# ESenseFE-Power.net
KiCad netlist of a schematic drawn in Altium Designer
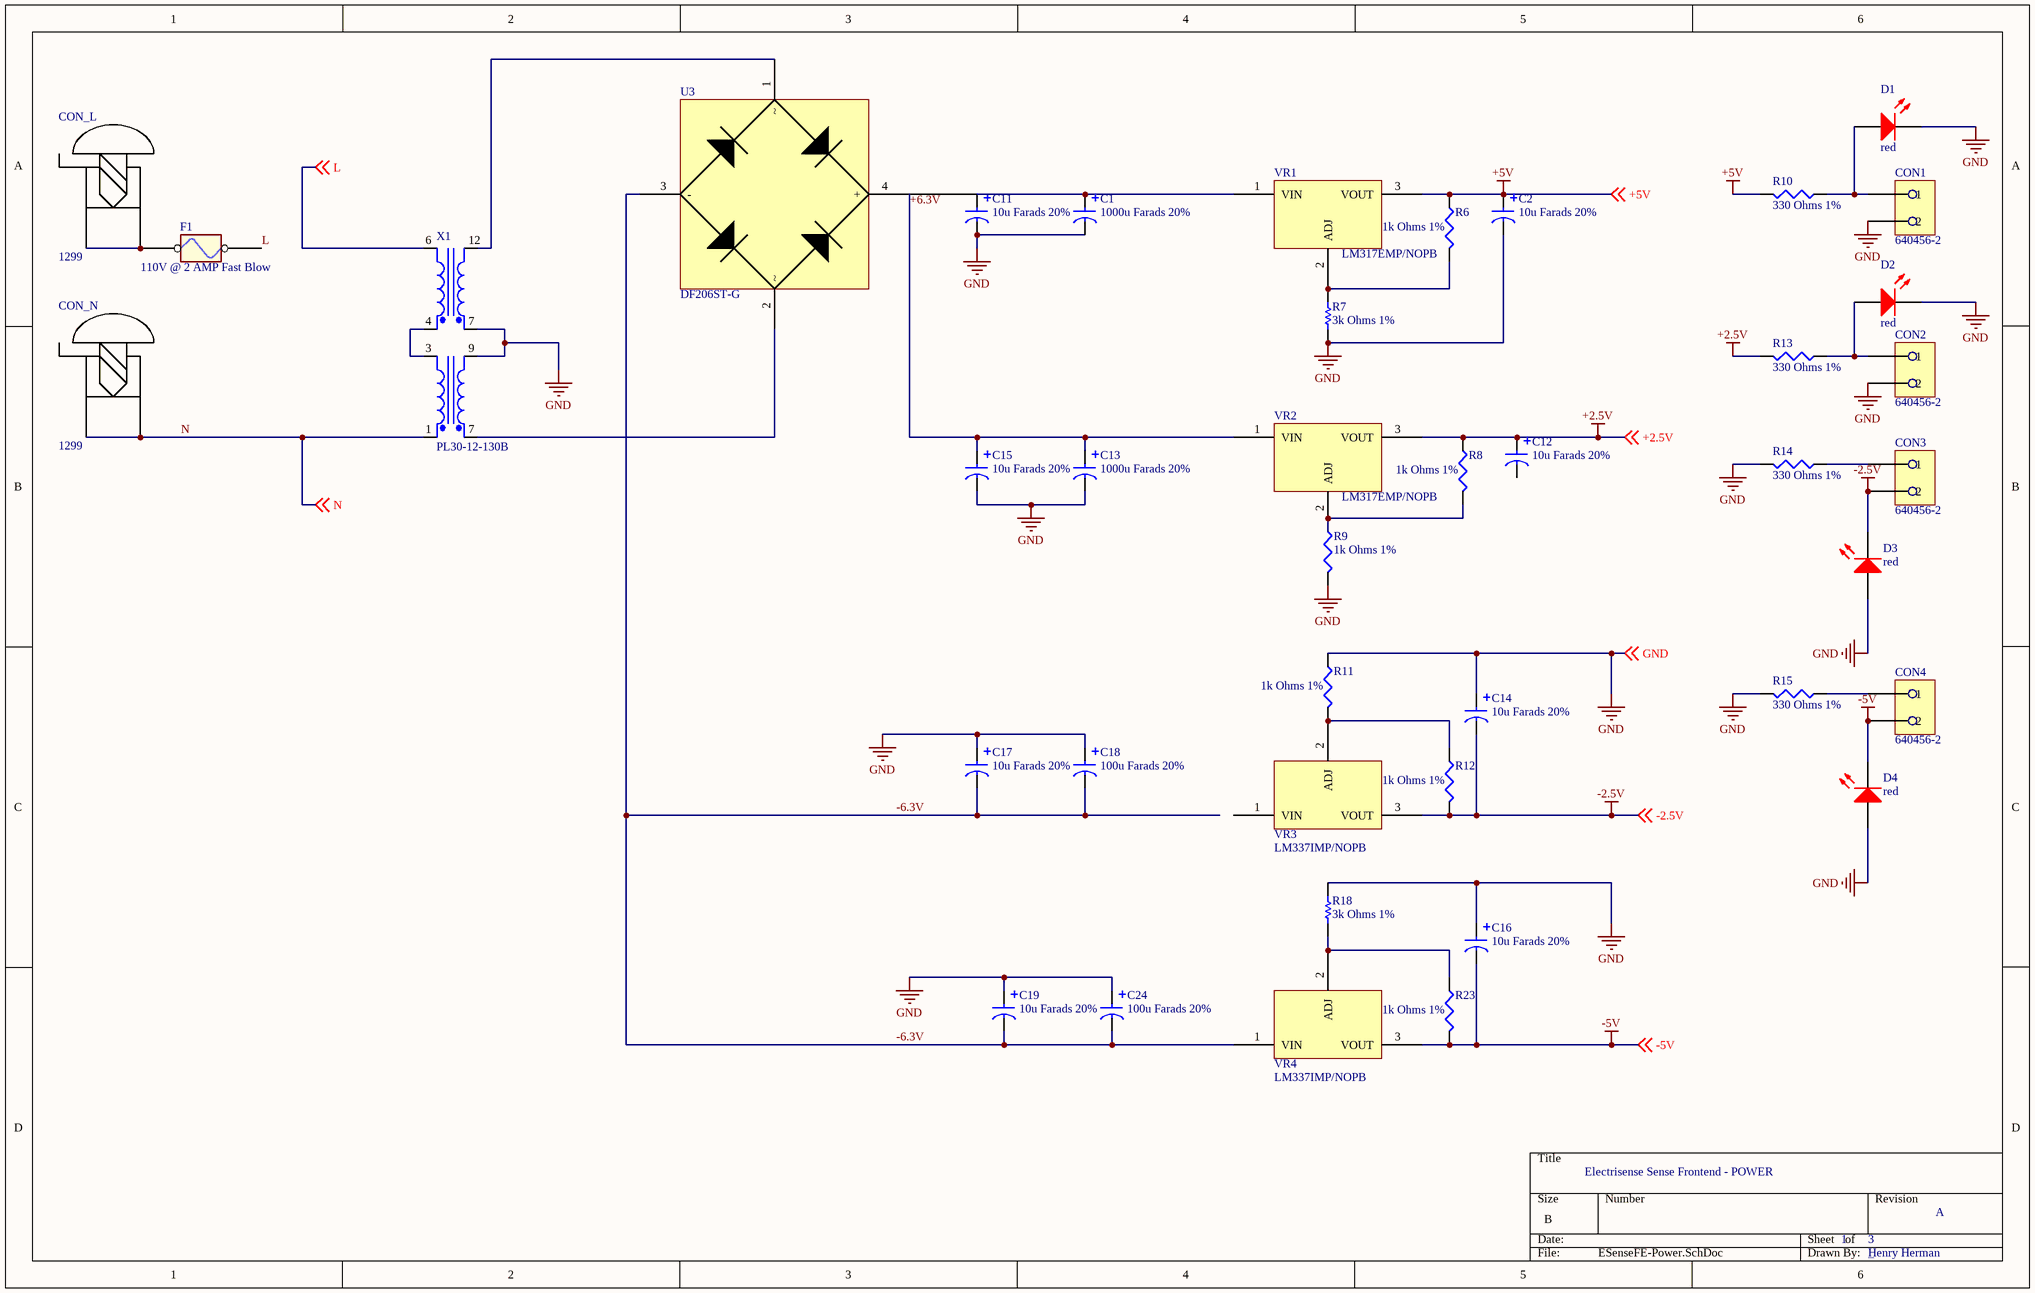
[diagram p0: ESenseFE-Power.SchDoc]

(export (version "E")
  (design (tool "Eeschema 10.0.6"))
  (components
    (comp (ref "C1")
      (value "1000u Farads 20%")
      (footprint "CAP-CAN-SMD-POL-12.5mmDia")
      (description "cap aluminum 1000uf 25vdc 20% 12.5 x 13.5mm smd 1100ma 5000")
      (fields (field (name "MFRPARTNUM") "EEV-FK1E102Q"))
      (libsource (lib "FriedParts") (part "CAP_POL"))
    )
    (comp (ref "C2")
      (value "10u Farads 20%")
      (footprint "CAP-SMD-POL-5mmDia")
      (description "capacitor, case c, 10uf, 25v; application:general purpose;")
      (fields (field (name "MFRPARTNUM") "EEE1EA100SR"))
      (libsource (lib "FriedParts") (part "CAP_POL"))
    )
    (comp (ref "C11")
      (value "10u Farads 20%")
      (footprint "CAP-SMD-POL-5mmDia")
      (description "capacitor, case c, 10uf, 25v; application:general purpose;")
      (fields (field (name "MFRPARTNUM") "EEE1EA100SR"))
      (libsource (lib "FriedParts") (part "CAP_POL"))
    )
    (comp (ref "C12")
      (value "10u Farads 20%")
      (footprint "CAP-SMD-POL-5mmDia")
      (description "capacitor, case c, 10uf, 25v; application:general purpose;")
      (fields (field (name "MFRPARTNUM") "EEE1EA100SR"))
      (libsource (lib "FriedParts") (part "CAP_POL"))
    )
    (comp (ref "C13")
      (value "1000u Farads 20%")
      (footprint "CAP-CAN-SMD-POL-12.5mmDia")
      (description "cap aluminum 1000uf 25vdc 20% 12.5 x 13.5mm smd 1100ma 5000")
      (fields (field (name "MFRPARTNUM") "EEV-FK1E102Q"))
      (libsource (lib "FriedParts") (part "CAP_POL"))
    )
    (comp (ref "C14")
      (value "10u Farads 20%")
      (footprint "CAP-SMD-POL-5mmDia")
      (description "capacitor, case c, 10uf, 25v; application:general purpose;")
      (fields (field (name "MFRPARTNUM") "EEE1EA100SR"))
      (libsource (lib "FriedParts") (part "CAP_POL"))
    )
    (comp (ref "C15")
      (value "10u Farads 20%")
      (footprint "CAP-SMD-POL-5mmDia")
      (description "capacitor, case c, 10uf, 25v; application:general purpose;")
      (fields (field (name "MFRPARTNUM") "EEE1EA100SR"))
      (libsource (lib "FriedParts") (part "CAP_POL"))
    )
    (comp (ref "C16")
      (value "10u Farads 20%")
      (footprint "CAP-SMD-POL-5mmDia")
      (description "capacitor, case c, 10uf, 25v; application:general purpose;")
      (fields (field (name "MFRPARTNUM") "EEE1EA100SR"))
      (libsource (lib "FriedParts") (part "CAP_POL"))
    )
    (comp (ref "C17")
      (value "10u Farads 20%")
      (footprint "CAP-SMD-POL-5mmDia")
      (description "capacitor, case c, 10uf, 25v; application:general purpose;")
      (fields (field (name "MFRPARTNUM") "EEE1EA100SR"))
      (libsource (lib "FriedParts") (part "CAP_POL"))
    )
    (comp (ref "C18")
      (value "100u Farads 20%")
      (footprint "CAP-SMD-POL-5mmDia")
      (description "cap 100uf 25vdc 20% 6.3 x 7.7mm smd 143ma 2000 hr t/r")
      (fields (field (name "MFRPARTNUM") "EEE-1EA101XP"))
      (libsource (lib "FriedParts") (part "CAP_POL"))
    )
    (comp (ref "C19")
      (value "10u Farads 20%")
      (footprint "CAP-SMD-POL-5mmDia")
      (description "capacitor, case c, 10uf, 25v; application:general purpose;")
      (fields (field (name "MFRPARTNUM") "EEE1EA100SR"))
      (libsource (lib "FriedParts") (part "CAP_POL"))
    )
    (comp (ref "C24")
      (value "100u Farads 20%")
      (footprint "CAP-SMD-POL-5mmDia")
      (description "cap 100uf 25vdc 20% 6.3 x 7.7mm smd 143ma 2000 hr t/r")
      (fields (field (name "MFRPARTNUM") "EEE-1EA101XP"))
      (libsource (lib "FriedParts") (part "CAP_POL"))
    )
    (comp (ref "CON1")
      (value "640456-2")
      (footprint "M02-LockingHeader-100mil-pitch")
      (description "header, vertical, 0.1``, 2way; connector type:wire-to-board;")
      (libsource (lib "FriedParts") (part "M02"))
    )
    (comp (ref "CON2")
      (value "640456-2")
      (footprint "M02-LockingHeader-100mil-pitch")
      (description "header, vertical, 0.1``, 2way; connector type:wire-to-board;")
      (libsource (lib "FriedParts") (part "M02"))
    )
    (comp (ref "CON3")
      (value "640456-2")
      (footprint "M02-LockingHeader-100mil-pitch")
      (description "header, vertical, 0.1``, 2way; connector type:wire-to-board;")
      (libsource (lib "FriedParts") (part "M02"))
    )
    (comp (ref "CON4")
      (value "640456-2")
      (footprint "M02-LockingHeader-100mil-pitch")
      (description "header, vertical, 0.1``, 2way; connector type:wire-to-board;")
      (libsource (lib "FriedParts") (part "M02"))
    )
    (comp (ref "CON_L")
      (value "1299")
      (footprint "LOW-PROFILE-SCREWTERMINAL")
      (description "brass tin plate low profile 10 - 32 thread with anti")
      (libsource (lib "FriedParts") (part "ScrewTerminal-PCB-ThruHole"))
    )
    (comp (ref "CON_N")
      (value "1299")
      (footprint "LOW-PROFILE-SCREWTERMINAL")
      (description "brass tin plate low profile 10 - 32 thread with anti")
      (libsource (lib "FriedParts") (part "ScrewTerminal-PCB-ThruHole"))
    )
    (comp (ref "D1")
      (value "red")
      (footprint "LITEON/LED/0603")
      (description "LED SUPER RED CLEAR 0603 SMD")
      (fields (field (name "MFRPARTNUM") "LTST-C190KRKT") (field (name "PUBLISHER") "Altium Limited"))
      (libsource (lib "FriedParts") (part "LITEON/LED RED"))
    )
    (comp (ref "D2")
      (value "red")
      (footprint "LITEON/LED/0603")
      (description "LED SUPER RED CLEAR 0603 SMD")
      (fields (field (name "MFRPARTNUM") "LTST-C190KRKT") (field (name "PUBLISHER") "Altium Limited"))
      (libsource (lib "FriedParts") (part "LITEON/LED RED"))
    )
    (comp (ref "D3")
      (value "red")
      (footprint "LITEON/LED/0603")
      (description "LED SUPER RED CLEAR 0603 SMD")
      (fields (field (name "MFRPARTNUM") "LTST-C190KRKT") (field (name "PUBLISHER") "Altium Limited"))
      (libsource (lib "FriedParts") (part "LITEON/LED RED"))
    )
    (comp (ref "D4")
      (value "red")
      (footprint "LITEON/LED/0603")
      (description "LED SUPER RED CLEAR 0603 SMD")
      (fields (field (name "MFRPARTNUM") "LTST-C190KRKT") (field (name "PUBLISHER") "Altium Limited"))
      (libsource (lib "FriedParts") (part "LITEON/LED RED"))
    )
    (comp (ref "F1")
      (value "110V @ 2 AMP Fast Blow")
      (footprint "WICKMANN/WK0011-ND")
      (description "FUSEHOLDER OPEN 5X20MM PC MNT")
      (fields (field (name "MFRPARTNUM") "6490000100"))
      (libsource (lib "FriedParts") (part "FUSEHOLDER"))
    )
    (comp (ref "R6")
      (value "1k Ohms 1%")
      (footprint "SM/C_0603")
      (description "RES 1.00K OHM 1/10W 1% 0603 SMD")
      (fields (field (name "MFRPARTNUM") "ERJ-3EKF1001V"))
      (libsource (lib "FriedParts") (part "R"))
    )
    (comp (ref "R7")
      (value "3k Ohms 1%")
      (footprint "SM/C_0603")
      (description "resistor, thick film, 30kohm, 100mw, 1%; resistance:30kohm;")
      (fields (field (name "MFRPARTNUM") "RC0603FR-0730KL") (field (name "PUBLISHER") "Altium Limited"))
      (libsource (lib "FriedParts") (part "Res1"))
    )
    (comp (ref "R8")
      (value "1k Ohms 1%")
      (footprint "SM/C_0603")
      (description "RES 1.00K OHM 1/10W 1% 0603 SMD")
      (fields (field (name "MFRPARTNUM") "ERJ-3EKF1001V"))
      (libsource (lib "FriedParts") (part "R"))
    )
    (comp (ref "R9")
      (value "1k Ohms 1%")
      (footprint "SM/C_0603")
      (description "RES 1.00K OHM 1/10W 1% 0603 SMD")
      (fields (field (name "MFRPARTNUM") "ERJ-3EKF1001V"))
      (libsource (lib "FriedParts") (part "R"))
    )
    (comp (ref "R10")
      (value "330 Ohms 1%")
      (footprint "SM/C_0603")
      (description "RES 330 OHM 1/10W 1% 0603 SMD")
      (fields (field (name "MFRPARTNUM") "ERJ-3EKF3300V"))
      (libsource (lib "FriedParts") (part "R"))
    )
    (comp (ref "R11")
      (value "1k Ohms 1%")
      (footprint "SM/C_0603")
      (description "RES 1.00K OHM 1/10W 1% 0603 SMD")
      (fields (field (name "MFRPARTNUM") "ERJ-3EKF1001V"))
      (libsource (lib "FriedParts") (part "R"))
    )
    (comp (ref "R12")
      (value "1k Ohms 1%")
      (footprint "SM/C_0603")
      (description "RES 1.00K OHM 1/10W 1% 0603 SMD")
      (fields (field (name "MFRPARTNUM") "ERJ-3EKF1001V"))
      (libsource (lib "FriedParts") (part "R"))
    )
    (comp (ref "R13")
      (value "330 Ohms 1%")
      (footprint "SM/C_0603")
      (description "RES 330 OHM 1/10W 1% 0603 SMD")
      (fields (field (name "MFRPARTNUM") "ERJ-3EKF3300V"))
      (libsource (lib "FriedParts") (part "R"))
    )
    (comp (ref "R14")
      (value "330 Ohms 1%")
      (footprint "SM/C_0603")
      (description "RES 330 OHM 1/10W 1% 0603 SMD")
      (fields (field (name "MFRPARTNUM") "ERJ-3EKF3300V"))
      (libsource (lib "FriedParts") (part "R"))
    )
    (comp (ref "R15")
      (value "330 Ohms 1%")
      (footprint "SM/C_0603")
      (description "RES 330 OHM 1/10W 1% 0603 SMD")
      (fields (field (name "MFRPARTNUM") "ERJ-3EKF3300V"))
      (libsource (lib "FriedParts") (part "R"))
    )
    (comp (ref "R18")
      (value "3k Ohms 1%")
      (footprint "SM/C_0603")
      (description "resistor, thick film, 30kohm, 100mw, 1%; resistance:30kohm;")
      (fields (field (name "MFRPARTNUM") "RC0603FR-0730KL") (field (name "PUBLISHER") "Altium Limited"))
      (libsource (lib "FriedParts") (part "Res1"))
    )
    (comp (ref "R23")
      (value "1k Ohms 1%")
      (footprint "SM/C_0603")
      (description "RES 1.00K OHM 1/10W 1% 0603 SMD")
      (fields (field (name "MFRPARTNUM") "ERJ-3EKF1001V"))
      (libsource (lib "FriedParts") (part "R"))
    )
    (comp (ref "U3")
      (value "DF206ST-G")
      (footprint "BridgeRectifier-DFS")
      (description "schottky diode; operating temperature range:0°c to +70°c;")
      (libsource (lib "FriedParts") (part "Bridge_Rectifier"))
    )
    (comp (ref "VR1")
      (value "LM317EMP/NOPB")
      (footprint "LM317-SOT233-POS-ADJ-VOLT_REG")
      (description "v reg, linear, 37v, smd; voltage regulator type:adjustable")
      (libsource (lib "FriedParts") (part "ADJ_VOLT_REG"))
    )
    (comp (ref "VR2")
      (value "LM317EMP/NOPB")
      (footprint "LM317-SOT233-POS-ADJ-VOLT_REG")
      (description "v reg, linear, 37v, smd; voltage regulator type:adjustable")
      (libsource (lib "FriedParts") (part "ADJ_VOLT_REG"))
    )
    (comp (ref "VR3")
      (value "LM337IMP/NOPB")
      (footprint "LM337-ADJ-NEG-VOLT-REG")
      (description "linear voltage regulator ic; output voltage adjustable")
      (libsource (lib "") (part "ADJ_VOLT_REG_1"))
    )
    (comp (ref "VR4")
      (value "LM337IMP/NOPB")
      (footprint "LM337-ADJ-NEG-VOLT-REG")
      (description "linear voltage regulator ic; output voltage adjustable")
      (libsource (lib "") (part "ADJ_VOLT_REG_1"))
    )
    (comp (ref "X1")
      (value "PL30-12-130B")
      (footprint "TRANSFORMER-DUAL-PRIMARY")
      (description "transformers 12.6vct @ 2.40a 6.3v @ 4.80a")
      (libsource (lib "FriedParts") (part "PowerTransformer-DualIput-Tamura-PL30-12-130B"))
    )
  )
  (nets
    (net (code "1") (name "+2.5V") (class "Default")
      (node (ref "C12") (pin "1") (pinfunction "1_1") (pintype "passive"))
      (node (ref "R13") (pin "2") (pinfunction "2_2") (pintype "passive"))
      (node (ref "R8") (pin "1") (pinfunction "1_1") (pintype "passive"))
      (node (ref "VR2") (pin "3") (pinfunction "VOUT_3") (pintype "passive"))
    )
    (net (code "2") (name "+5V") (class "Default")
      (node (ref "C2") (pin "1") (pinfunction "1_1") (pintype "passive"))
      (node (ref "R10") (pin "2") (pinfunction "2_2") (pintype "passive"))
      (node (ref "R6") (pin "1") (pinfunction "1_1") (pintype "passive"))
      (node (ref "VR1") (pin "3") (pinfunction "VOUT_3") (pintype "passive"))
    )
    (net (code "3") (name "-2.5V") (class "Default")
      (node (ref "C14") (pin "2") (pinfunction "2_2") (pintype "passive"))
      (node (ref "CON3") (pin "2") (pinfunction "2_2") (pintype "passive"))
      (node (ref "D3") (pin "2") (pinfunction "K_2") (pintype "passive"))
      (node (ref "R12") (pin "2") (pinfunction "2_2") (pintype "passive"))
      (node (ref "VR3") (pin "3") (pinfunction "VOUT_3") (pintype "passive"))
    )
    (net (code "4") (name "-5V") (class "Default")
      (node (ref "C16") (pin "2") (pinfunction "2_2") (pintype "passive"))
      (node (ref "CON4") (pin "2") (pinfunction "2_2") (pintype "passive"))
      (node (ref "D4") (pin "2") (pinfunction "K_2") (pintype "passive"))
      (node (ref "R23") (pin "2") (pinfunction "2_2") (pintype "passive"))
      (node (ref "VR4") (pin "3") (pinfunction "VOUT_3") (pintype "passive"))
    )
    (net (code "5") (name "/+6.3V") (class "Default")
      (node (ref "C13") (pin "1") (pinfunction "1_1") (pintype "passive"))
      (node (ref "C15") (pin "1") (pinfunction "1_1") (pintype "passive"))
      (node (ref "U3") (pin "4") (pinfunction "+_4") (pintype "passive"))
      (node (ref "VR2") (pin "1") (pinfunction "VIN_1") (pintype "passive"))
    )
    (net (code "6") (name "/-6.3V") (class "Default")
      (node (ref "C17") (pin "2") (pinfunction "2_2") (pintype "passive"))
      (node (ref "C18") (pin "2") (pinfunction "2_2") (pintype "passive"))
      (node (ref "C19") (pin "2") (pinfunction "2_2") (pintype "passive"))
      (node (ref "C24") (pin "2") (pinfunction "2_2") (pintype "passive"))
      (node (ref "U3") (pin "3") (pinfunction "-_3") (pintype "passive"))
      (node (ref "VR4") (pin "1") (pinfunction "VIN_1") (pintype "passive"))
    )
    (net (code "7") (name "GND") (class "Default")
      (node (ref "C1") (pin "2") (pinfunction "2_2") (pintype "passive"))
      (node (ref "C11") (pin "2") (pinfunction "2_2") (pintype "passive"))
      (node (ref "C13") (pin "2") (pinfunction "2_2") (pintype "passive"))
      (node (ref "C14") (pin "1") (pinfunction "1_1") (pintype "passive"))
      (node (ref "C15") (pin "2") (pinfunction "2_2") (pintype "passive"))
      (node (ref "C16") (pin "1") (pinfunction "1_1") (pintype "passive"))
      (node (ref "C17") (pin "1") (pinfunction "1_1") (pintype "passive"))
      (node (ref "C18") (pin "1") (pinfunction "1_1") (pintype "passive"))
      (node (ref "C19") (pin "1") (pinfunction "1_1") (pintype "passive"))
      (node (ref "C2") (pin "2") (pinfunction "2_2") (pintype "passive"))
      (node (ref "C24") (pin "1") (pinfunction "1_1") (pintype "passive"))
      (node (ref "CON1") (pin "2") (pinfunction "2_2") (pintype "passive"))
      (node (ref "CON2") (pin "2") (pinfunction "2_2") (pintype "passive"))
      (node (ref "D1") (pin "2") (pinfunction "K_2") (pintype "passive"))
      (node (ref "D2") (pin "2") (pinfunction "K_2") (pintype "passive"))
      (node (ref "D3") (pin "1") (pinfunction "A_1") (pintype "passive"))
      (node (ref "D4") (pin "1") (pinfunction "A_1") (pintype "passive"))
      (node (ref "R11") (pin "1") (pinfunction "1_1") (pintype "passive"))
      (node (ref "R14") (pin "2") (pinfunction "2_2") (pintype "passive"))
      (node (ref "R15") (pin "2") (pinfunction "2_2") (pintype "passive"))
      (node (ref "R18") (pin "2") (pinfunction "2_2") (pintype "passive"))
      (node (ref "R7") (pin "1") (pinfunction "1_1") (pintype "passive"))
      (node (ref "R9") (pin "2") (pinfunction "2_2") (pintype "passive"))
      (node (ref "X1") (pin "7") (pinfunction "10_7") (pintype "passive"))
      (node (ref "X1") (pin "9") (pinfunction "7_9") (pintype "passive"))
    )
    (net (code "8") (name "L") (class "Default")
      (node (ref "F1") (pin "2") (pinfunction "2_2") (pintype "passive"))
      (node (ref "X1") (pin "6") (pinfunction "Pri-_6") (pintype "passive"))
    )
    (net (code "9") (name "N") (class "Default")
      (node (ref "CON_N") (pin "1") (pintype "passive"))
      (node (ref "X1") (pin "1") (pinfunction "Pri+_1") (pintype "passive"))
    )
    (net (code "10") (name "Net-(CON3-Pad1)") (class "Default")
      (node (ref "CON3") (pin "1") (pinfunction "1_1") (pintype "passive"))
      (node (ref "R14") (pin "1") (pinfunction "1_1") (pintype "passive"))
    )
    (net (code "11") (name "Net-(CON4-Pad1)") (class "Default")
      (node (ref "CON4") (pin "1") (pinfunction "1_1") (pintype "passive"))
      (node (ref "R15") (pin "1") (pinfunction "1_1") (pintype "passive"))
    )
    (net (code "12") (name "Net-(CON_L-Pad1)") (class "Default")
      (node (ref "CON_L") (pin "1") (pintype "passive"))
      (node (ref "F1") (pin "1") (pinfunction "1_1") (pintype "passive"))
    )
    (net (code "13") (name "Net-(D1-A)") (class "Default")
      (node (ref "CON1") (pin "1") (pinfunction "1_1") (pintype "passive"))
      (node (ref "D1") (pin "1") (pinfunction "A_1") (pintype "passive"))
      (node (ref "R10") (pin "1") (pinfunction "1_1") (pintype "passive"))
    )
    (net (code "14") (name "Net-(D2-A)") (class "Default")
      (node (ref "CON2") (pin "1") (pinfunction "1_1") (pintype "passive"))
      (node (ref "D2") (pin "1") (pinfunction "A_1") (pintype "passive"))
      (node (ref "R13") (pin "1") (pinfunction "1_1") (pintype "passive"))
    )
    (net (code "15") (name "Net-(VR1-ADJ)") (class "Default")
      (node (ref "R6") (pin "2") (pinfunction "2_2") (pintype "passive"))
      (node (ref "R7") (pin "2") (pinfunction "2_2") (pintype "passive"))
      (node (ref "VR1") (pin "2") (pinfunction "ADJ_2") (pintype "passive"))
    )
    (net (code "16") (name "Net-(VR1-VIN)") (class "Default")
      (node (ref "C1") (pin "1") (pinfunction "1_1") (pintype "passive"))
      (node (ref "C11") (pin "1") (pinfunction "1_1") (pintype "passive"))
      (node (ref "VR1") (pin "1") (pinfunction "VIN_1") (pintype "passive"))
    )
    (net (code "17") (name "Net-(VR2-ADJ)") (class "Default")
      (node (ref "R8") (pin "2") (pinfunction "2_2") (pintype "passive"))
      (node (ref "R9") (pin "1") (pinfunction "1_1") (pintype "passive"))
      (node (ref "VR2") (pin "2") (pinfunction "ADJ_2") (pintype "passive"))
    )
    (net (code "18") (name "Net-(VR3-ADJ)") (class "Default")
      (node (ref "R11") (pin "2") (pinfunction "2_2") (pintype "passive"))
      (node (ref "R12") (pin "1") (pinfunction "1_1") (pintype "passive"))
      (node (ref "VR3") (pin "2") (pinfunction "ADJ_2") (pintype "passive"))
    )
    (net (code "19") (name "Net-(VR4-ADJ)") (class "Default")
      (node (ref "R18") (pin "1") (pinfunction "1_1") (pintype "passive"))
      (node (ref "R23") (pin "1") (pinfunction "1_1") (pintype "passive"))
      (node (ref "VR4") (pin "2") (pinfunction "ADJ_2") (pintype "passive"))
    )
    (net (code "20") (name "Net-(X1-Pri+-Pad4)") (class "Default")
      (node (ref "X1") (pin "3") (pinfunction "Pri-_3") (pintype "passive"))
      (node (ref "X1") (pin "4") (pinfunction "Pri+_4") (pintype "passive"))
    )
    (net (code "21") (name "Net-(X1-Sec+)") (class "Default")
      (node (ref "U3") (pin "2") (pinfunction "~_2") (pintype "passive"))
      (node (ref "X1") (pin "7") (pinfunction "Sec+_7") (pintype "passive"))
    )
    (net (code "22") (name "Net-(X1-Sec-)") (class "Default")
      (node (ref "U3") (pin "1") (pinfunction "~_1") (pintype "passive"))
      (node (ref "X1") (pin "12") (pinfunction "Sec-_12") (pintype "passive"))
    )
    (net (code "23") (name "unconnected-(C12-Pad2)") (class "Default")
      (node (ref "C12") (pin "2") (pinfunction "2_2") (pintype "passive"))
    )
    (net (code "24") (name "unconnected-(VR3-VIN-Pad1)") (class "Default")
      (node (ref "VR3") (pin "1") (pinfunction "VIN_1") (pintype "passive"))
    )
  )
)
